# strip10.net
KiCad netlist of a schematic drawn in EAGLE
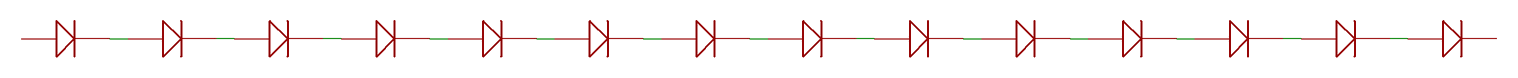
[diagram p0: schematic, sheet 1]

(export (version "E")
  (design (tool "Eeschema 10.0.6"))
  (components
    (comp (ref "U$1")
      (value "JDSTS2.EM-HRHT-XX52-1")
      (footprint "eagle-import:JDSTS2.EM-HRHT-XX52-1")
      (libsource (lib "eagle-import") (part "JDSTS2.EM-HRHT-XX52-1"))
    )
    (comp (ref "U$2")
      (value "JDSTS2.EM-HRHT-XX52-1")
      (footprint "eagle-import:JDSTS2.EM-HRHT-XX52-1")
      (libsource (lib "eagle-import") (part "JDSTS2.EM-HRHT-XX52-1"))
    )
    (comp (ref "U$3")
      (value "JDSTS2.EM-HRHT-XX52-1")
      (footprint "eagle-import:JDSTS2.EM-HRHT-XX52-1")
      (libsource (lib "eagle-import") (part "JDSTS2.EM-HRHT-XX52-1"))
    )
    (comp (ref "U$4")
      (value "JDSTS2.EM-HRHT-XX52-1")
      (footprint "eagle-import:JDSTS2.EM-HRHT-XX52-1")
      (libsource (lib "eagle-import") (part "JDSTS2.EM-HRHT-XX52-1"))
    )
    (comp (ref "U$5")
      (value "JDSTS2.EM-HRHT-XX52-1")
      (footprint "eagle-import:JDSTS2.EM-HRHT-XX52-1")
      (libsource (lib "eagle-import") (part "JDSTS2.EM-HRHT-XX52-1"))
    )
    (comp (ref "U$6")
      (value "JDSTS2.EM-HRHT-XX52-1")
      (footprint "eagle-import:JDSTS2.EM-HRHT-XX52-1")
      (libsource (lib "eagle-import") (part "JDSTS2.EM-HRHT-XX52-1"))
    )
    (comp (ref "U$7")
      (value "JDSTS2.EM-HRHT-XX52-1")
      (footprint "eagle-import:JDSTS2.EM-HRHT-XX52-1")
      (libsource (lib "eagle-import") (part "JDSTS2.EM-HRHT-XX52-1"))
    )
    (comp (ref "U$8")
      (value "JDSTS2.EM-HRHT-XX52-1")
      (footprint "eagle-import:JDSTS2.EM-HRHT-XX52-1")
      (libsource (lib "eagle-import") (part "JDSTS2.EM-HRHT-XX52-1"))
    )
    (comp (ref "U$9")
      (value "JDSTS2.EM-HRHT-XX52-1")
      (footprint "eagle-import:JDSTS2.EM-HRHT-XX52-1")
      (libsource (lib "eagle-import") (part "JDSTS2.EM-HRHT-XX52-1"))
    )
    (comp (ref "U$10")
      (value "JDSTS2.EM-HRHT-XX52-1")
      (footprint "eagle-import:JDSTS2.EM-HRHT-XX52-1")
      (libsource (lib "eagle-import") (part "JDSTS2.EM-HRHT-XX52-1"))
    )
    (comp (ref "U$11")
      (value "JDSTS2.EM-HRHT-XX52-1")
      (footprint "eagle-import:JDSTS2.EM-HRHT-XX52-1")
      (libsource (lib "eagle-import") (part "JDSTS2.EM-HRHT-XX52-1"))
    )
    (comp (ref "U$12")
      (value "JDSTS2.EM-HRHT-XX52-1")
      (footprint "eagle-import:JDSTS2.EM-HRHT-XX52-1")
      (libsource (lib "eagle-import") (part "JDSTS2.EM-HRHT-XX52-1"))
    )
    (comp (ref "U$13")
      (value "JDSTS2.EM-HRHT-XX52-1")
      (footprint "eagle-import:JDSTS2.EM-HRHT-XX52-1")
      (libsource (lib "eagle-import") (part "JDSTS2.EM-HRHT-XX52-1"))
    )
    (comp (ref "U$14")
      (value "JDSTS2.EM-HRHT-XX52-1")
      (footprint "eagle-import:JDSTS2.EM-HRHT-XX52-1")
      (libsource (lib "eagle-import") (part "JDSTS2.EM-HRHT-XX52-1"))
    )
  )
  (nets
    (net (code "1") (name "Net-(U$1-P$2)") (class "Default")
      (node (ref "U$1") (pin "3V") (pinfunction "P$2_3V") (pintype "bidirectional"))
      (node (ref "U$2") (pin "GND") (pinfunction "P$1_GND") (pintype "bidirectional"))
    )
    (net (code "2") (name "Net-(U$2-P$2)") (class "Default")
      (node (ref "U$2") (pin "3V") (pinfunction "P$2_3V") (pintype "bidirectional"))
      (node (ref "U$3") (pin "GND") (pinfunction "P$1_GND") (pintype "bidirectional"))
    )
    (net (code "3") (name "Net-(U$3-P$2)") (class "Default")
      (node (ref "U$3") (pin "3V") (pinfunction "P$2_3V") (pintype "bidirectional"))
      (node (ref "U$4") (pin "GND") (pinfunction "P$1_GND") (pintype "bidirectional"))
    )
    (net (code "4") (name "Net-(U$4-P$2)") (class "Default")
      (node (ref "U$4") (pin "3V") (pinfunction "P$2_3V") (pintype "bidirectional"))
      (node (ref "U$5") (pin "GND") (pinfunction "P$1_GND") (pintype "bidirectional"))
    )
    (net (code "5") (name "Net-(U$5-P$2)") (class "Default")
      (node (ref "U$5") (pin "3V") (pinfunction "P$2_3V") (pintype "bidirectional"))
      (node (ref "U$6") (pin "GND") (pinfunction "P$1_GND") (pintype "bidirectional"))
    )
    (net (code "6") (name "Net-(U$6-P$2)") (class "Default")
      (node (ref "U$6") (pin "3V") (pinfunction "P$2_3V") (pintype "bidirectional"))
      (node (ref "U$7") (pin "GND") (pinfunction "P$1_GND") (pintype "bidirectional"))
    )
    (net (code "7") (name "Net-(U$7-P$2)") (class "Default")
      (node (ref "U$7") (pin "3V") (pinfunction "P$2_3V") (pintype "bidirectional"))
      (node (ref "U$8") (pin "GND") (pinfunction "P$1_GND") (pintype "bidirectional"))
    )
    (net (code "8") (name "Net-(U$8-P$2)") (class "Default")
      (node (ref "U$8") (pin "3V") (pinfunction "P$2_3V") (pintype "bidirectional"))
      (node (ref "U$9") (pin "GND") (pinfunction "P$1_GND") (pintype "bidirectional"))
    )
    (net (code "9") (name "Net-(U$10-P$1)") (class "Default")
      (node (ref "U$10") (pin "GND") (pinfunction "P$1_GND") (pintype "bidirectional"))
      (node (ref "U$9") (pin "3V") (pinfunction "P$2_3V") (pintype "bidirectional"))
    )
    (net (code "10") (name "Net-(U$10-P$2)") (class "Default")
      (node (ref "U$10") (pin "3V") (pinfunction "P$2_3V") (pintype "bidirectional"))
      (node (ref "U$11") (pin "GND") (pinfunction "P$1_GND") (pintype "bidirectional"))
    )
    (net (code "11") (name "Net-(U$11-P$2)") (class "Default")
      (node (ref "U$11") (pin "3V") (pinfunction "P$2_3V") (pintype "bidirectional"))
      (node (ref "U$12") (pin "GND") (pinfunction "P$1_GND") (pintype "bidirectional"))
    )
    (net (code "12") (name "Net-(U$12-P$2)") (class "Default")
      (node (ref "U$12") (pin "3V") (pinfunction "P$2_3V") (pintype "bidirectional"))
      (node (ref "U$13") (pin "GND") (pinfunction "P$1_GND") (pintype "bidirectional"))
    )
    (net (code "13") (name "Net-(U$13-P$2)") (class "Default")
      (node (ref "U$13") (pin "3V") (pinfunction "P$2_3V") (pintype "bidirectional"))
      (node (ref "U$14") (pin "GND") (pinfunction "P$1_GND") (pintype "bidirectional"))
    )
    (net (code "14") (name "unconnected-(U$1-P$1-PadGND)") (class "Default")
      (node (ref "U$1") (pin "GND") (pinfunction "P$1_GND") (pintype "bidirectional"))
    )
    (net (code "15") (name "unconnected-(U$14-P$2-Pad3V)") (class "Default")
      (node (ref "U$14") (pin "3V") (pinfunction "P$2_3V") (pintype "bidirectional"))
    )
  )
)
